# PA_CTRL_TOP.net
KiCad netlist of a schematic drawn in Altium Designer
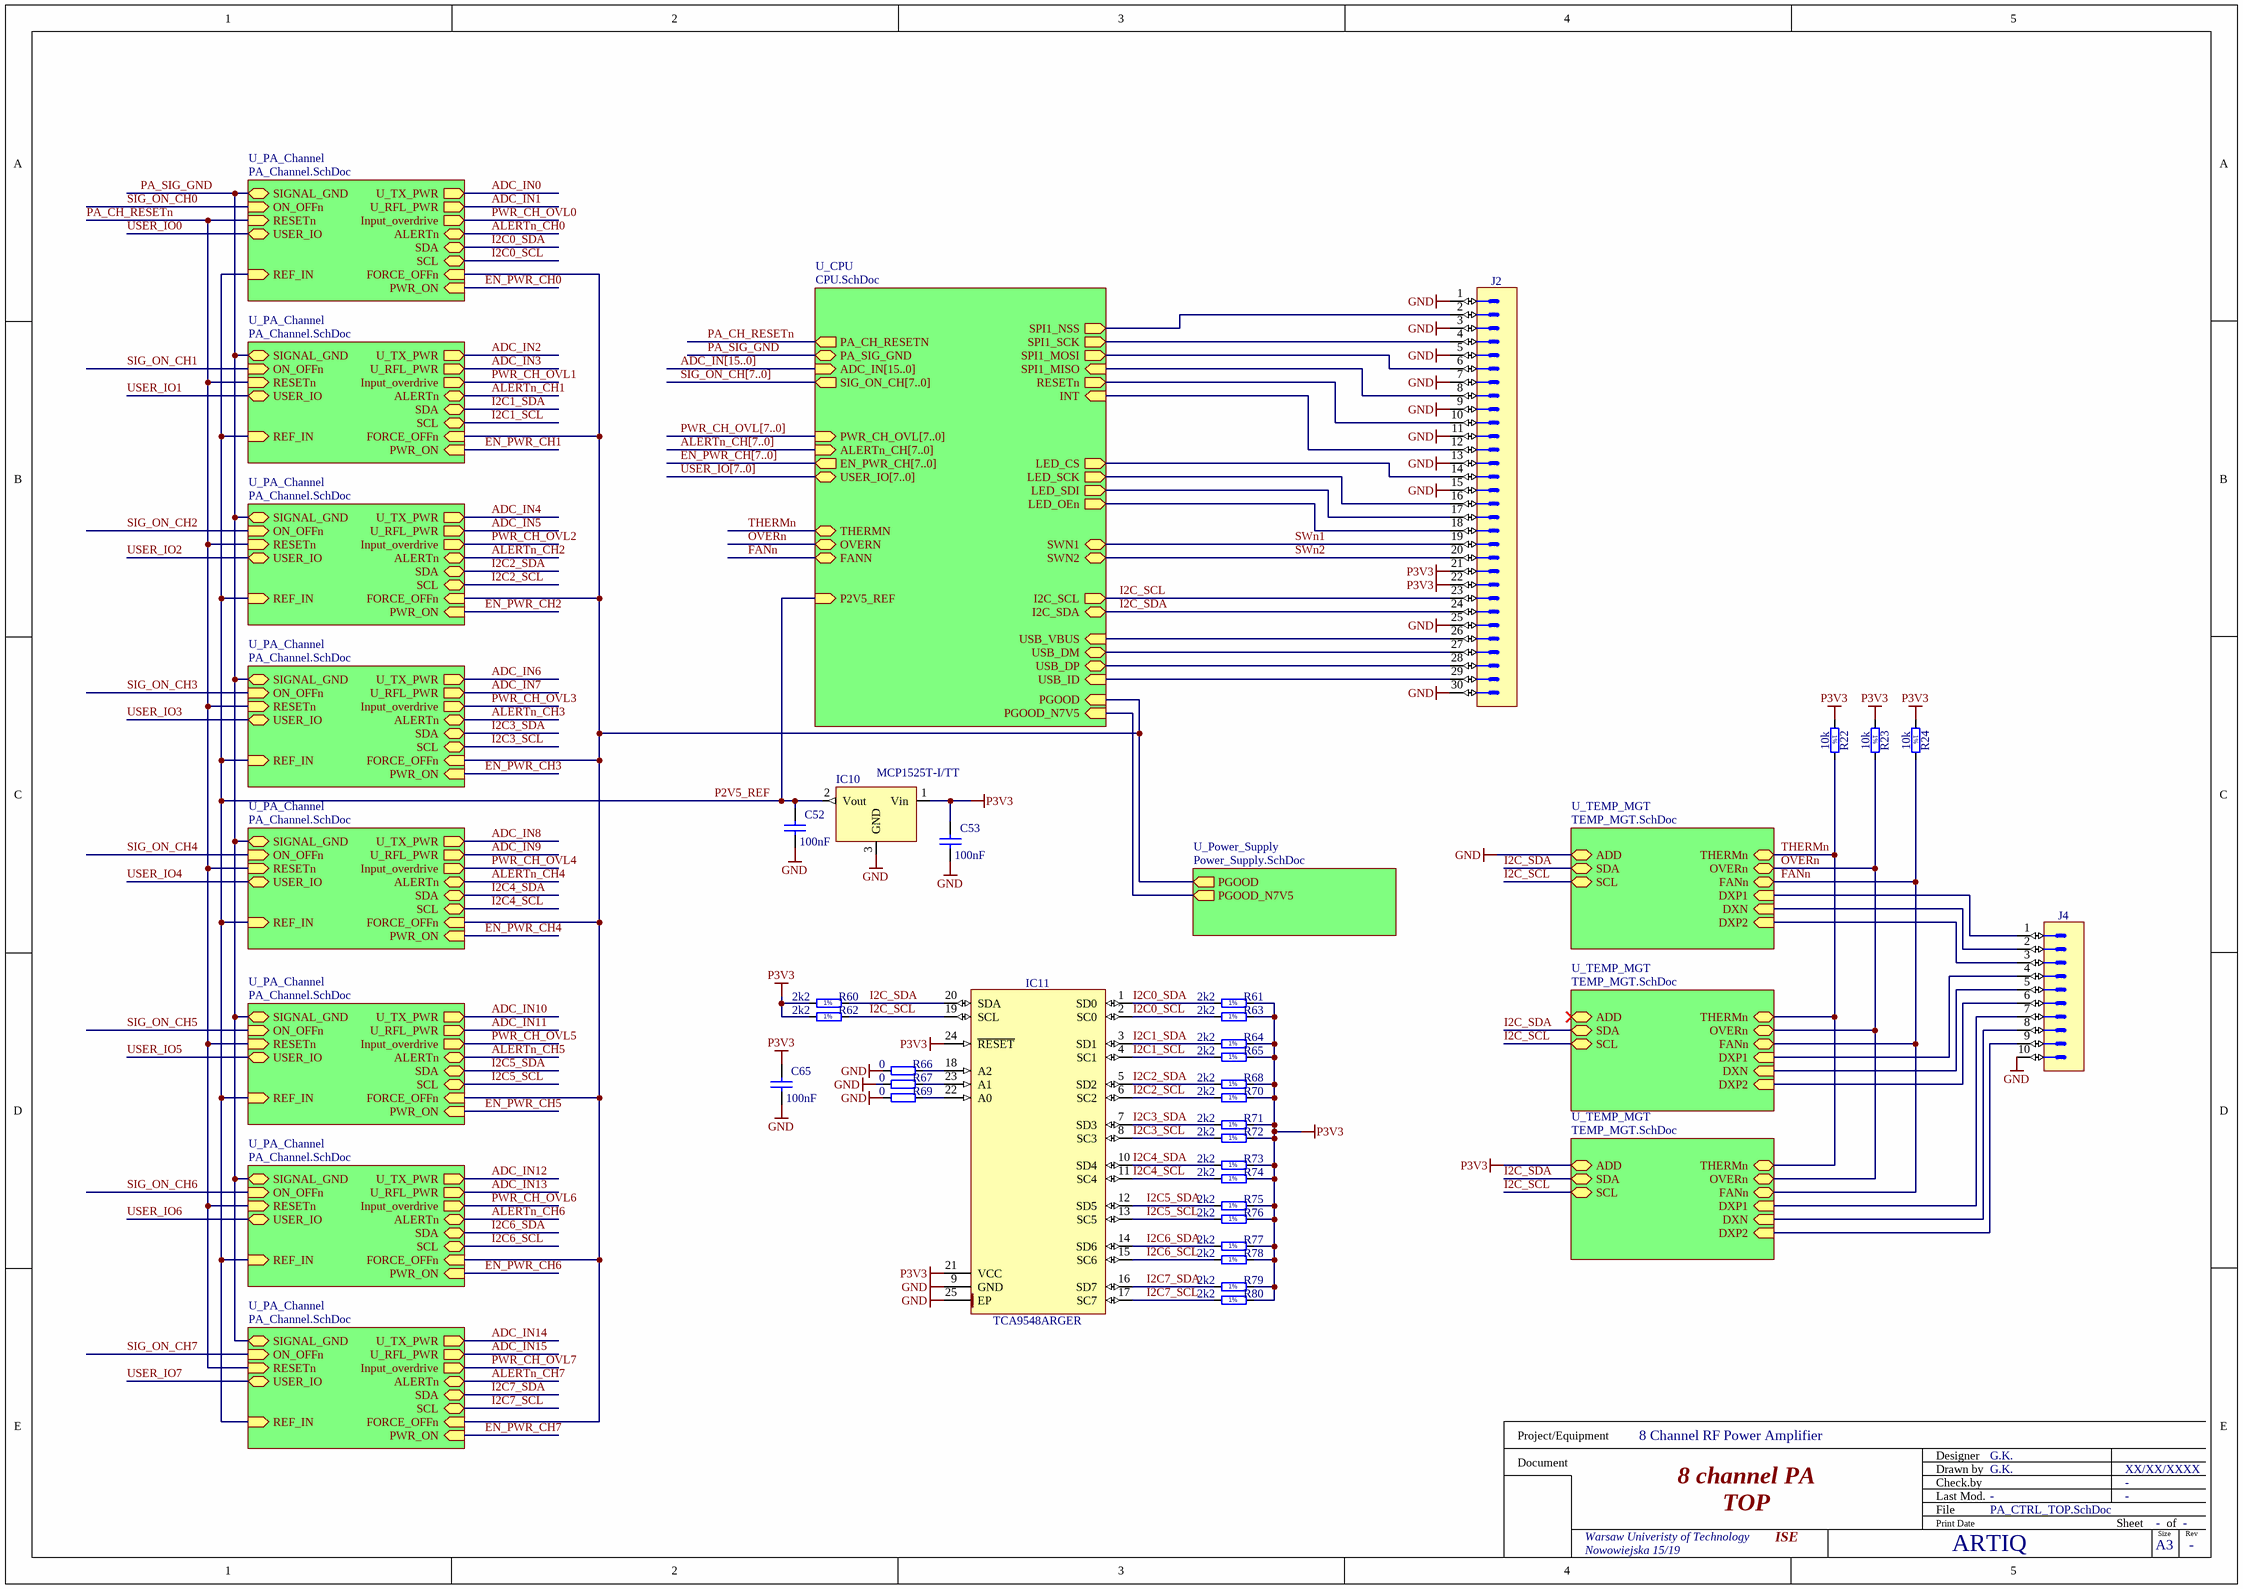
[diagram p0: PA_CTRL_TOP.SchDoc]

(export (version "E")
  (design (tool "Eeschema 10.0.6"))
  (components
    (comp (ref "C52")
      (value "100nF")
      (footprint "CAPC1005X55N")
      (description "Non-polarised capacitor")
      (fields
        (field (name "PART NUMBER") "CC0402_100NF_16V_10%_X7R")
        (field (name "VOLTAGE") "16V")
        (field (name "AUTHOR") "CERN DEM JLC")
      )
      (libsource (lib "Capacitors") (part "Capacitor - non polarized"))
    )
    (comp (ref "C53")
      (value "100nF")
      (footprint "CAPC1005X55N")
      (description "Non-polarised capacitor")
      (fields
        (field (name "PART NUMBER") "CC0402_100NF_16V_10%_X7R")
        (field (name "VOLTAGE") "16V")
        (field (name "AUTHOR") "CERN DEM JLC")
      )
      (libsource (lib "Capacitors") (part "Capacitor - non polarized"))
    )
    (comp (ref "C65")
      (value "100nF")
      (footprint "CAPC1005X55N")
      (description "Non-polarised capacitor")
      (fields
        (field (name "PART NUMBER") "CC0402_100NF_16V_10%_X7R")
        (field (name "VOLTAGE") "16V")
        (field (name "AUTHOR") "CERN DEM JLC")
      )
      (libsource (lib "Capacitors") (part "Capacitor - non polarized"))
    )
    (comp (ref "IC10")
      (value "MCP1525T-I/TT")
      (footprint "SOT95P251X112-3N")
      (description "2.5 voltage reference")
      (libsource (lib "LIBRARY_SCH") (part "REF_MCP1525"))
    )
    (comp (ref "IC11")
      (value "TCA9548ARGER")
      (footprint "QFN50P400X400X100-25N-S220")
      (description "Low Voltage 8-Channel I2C Switch With Reset")
      (fields (field (name "MANUFACTURER") "TEXAS INSTRUMENTS") (field (name "AUTHOR") "CERN DEM JLC"))
      (libsource (lib "ICs And Semiconductors") (part "TCA9548ARGER"))
    )
    (comp (ref "J2")
      (value "~")
      (footprint "3M_N2530-6002RB")
      (description "Connector 30 Male")
      (fields
        (field (name "PART NUMBER") "3M_N2530-6002RB")
        (field (name "MANUFACTURER") "3M")
        (field (name "AUTHOR") "CERN DEM JLC")
      )
      (libsource (lib "Connectors") (part "Connector 30 Male"))
    )
    (comp (ref "J4")
      (value "Header 10")
      (footprint "3M_N2510-6003RB")
      (description "Connector 10 Male")
      (fields
        (field (name "PART NUMBER") "3M_N2510-6003RB")
        (field (name "MANUFACTURER") "3M")
        (field (name "AUTHOR") "CERN DEM JLC")
      )
      (libsource (lib "Connectors") (part "Connector 10 Male"))
    )
    (comp (ref "R22")
      (value "10k")
      (footprint "RESC1005X40N")
      (description "Resistor - 1%")
      (fields
        (field (name "PART NUMBER") "R0402_10K_1%_0.0625W_100PPM")
        (field (name "POWER") "0.0625W")
        (field (name "AUTHOR") "CERN DEM JLC")
      )
      (libsource (lib "Resistors") (part "Resistor - 1%"))
    )
    (comp (ref "R23")
      (value "10k")
      (footprint "RESC1005X40N")
      (description "Resistor - 1%")
      (fields
        (field (name "PART NUMBER") "R0402_10K_1%_0.0625W_100PPM")
        (field (name "POWER") "0.0625W")
        (field (name "AUTHOR") "CERN DEM JLC")
      )
      (libsource (lib "Resistors") (part "Resistor - 1%"))
    )
    (comp (ref "R24")
      (value "10k")
      (footprint "RESC1005X40N")
      (description "Resistor - 1%")
      (fields
        (field (name "PART NUMBER") "R0402_10K_1%_0.0625W_100PPM")
        (field (name "POWER") "0.0625W")
        (field (name "AUTHOR") "CERN DEM JLC")
      )
      (libsource (lib "Resistors") (part "Resistor - 1%"))
    )
    (comp (ref "R60")
      (value "2k2")
      (footprint "RESC1005X40N")
      (description "Resistor - 1%")
      (fields
        (field (name "PART NUMBER") "R0402_2K2_1%_0.0625W_100PPM")
        (field (name "POWER") "0.0625W")
        (field (name "AUTHOR") "CERN DEM JLC")
      )
      (libsource (lib "Resistors") (part "Resistor - 1%"))
    )
    (comp (ref "R61")
      (value "2k2")
      (footprint "RESC1005X40N")
      (description "Resistor - 1%")
      (fields
        (field (name "PART NUMBER") "R0402_2K2_1%_0.0625W_100PPM")
        (field (name "POWER") "0.0625W")
        (field (name "AUTHOR") "CERN DEM JLC")
      )
      (libsource (lib "Resistors") (part "Resistor - 1%"))
    )
    (comp (ref "R62")
      (value "2k2")
      (footprint "RESC1005X40N")
      (description "Resistor - 1%")
      (fields
        (field (name "PART NUMBER") "R0402_2K2_1%_0.0625W_100PPM")
        (field (name "POWER") "0.0625W")
        (field (name "AUTHOR") "CERN DEM JLC")
      )
      (libsource (lib "Resistors") (part "Resistor - 1%"))
    )
    (comp (ref "R63")
      (value "2k2")
      (footprint "RESC1005X40N")
      (description "Resistor - 1%")
      (fields
        (field (name "PART NUMBER") "R0402_2K2_1%_0.0625W_100PPM")
        (field (name "POWER") "0.0625W")
        (field (name "AUTHOR") "CERN DEM JLC")
      )
      (libsource (lib "Resistors") (part "Resistor - 1%"))
    )
    (comp (ref "R64")
      (value "2k2")
      (footprint "RESC1005X40N")
      (description "Resistor - 1%")
      (fields
        (field (name "PART NUMBER") "R0402_2K2_1%_0.0625W_100PPM")
        (field (name "POWER") "0.0625W")
        (field (name "AUTHOR") "CERN DEM JLC")
      )
      (libsource (lib "Resistors") (part "Resistor - 1%"))
    )
    (comp (ref "R65")
      (value "2k2")
      (footprint "RESC1005X40N")
      (description "Resistor - 1%")
      (fields
        (field (name "PART NUMBER") "R0402_2K2_1%_0.0625W_100PPM")
        (field (name "POWER") "0.0625W")
        (field (name "AUTHOR") "CERN DEM JLC")
      )
      (libsource (lib "Resistors") (part "Resistor - 1%"))
    )
    (comp (ref "R66")
      (value "0")
      (footprint "RESC1005X40N")
      (description "Resistor")
      (fields
        (field (name "PART NUMBER") "R0402_0R_JUMPER")
        (field (name "MANUFACTURER") "GENERIC")
        (field (name "AUTHOR") "CERN DEM JLC")
      )
      (libsource (lib "Resistors") (part "Resistor"))
    )
    (comp (ref "R67")
      (value "0")
      (footprint "RESC1005X40N")
      (description "Resistor")
      (fields
        (field (name "PART NUMBER") "R0402_0R_JUMPER")
        (field (name "MANUFACTURER") "GENERIC")
        (field (name "AUTHOR") "CERN DEM JLC")
      )
      (libsource (lib "Resistors") (part "Resistor"))
    )
    (comp (ref "R68")
      (value "2k2")
      (footprint "RESC1005X40N")
      (description "Resistor - 1%")
      (fields
        (field (name "PART NUMBER") "R0402_2K2_1%_0.0625W_100PPM")
        (field (name "POWER") "0.0625W")
        (field (name "AUTHOR") "CERN DEM JLC")
      )
      (libsource (lib "Resistors") (part "Resistor - 1%"))
    )
    (comp (ref "R69")
      (value "0")
      (footprint "RESC1005X40N")
      (description "Resistor")
      (fields
        (field (name "PART NUMBER") "R0402_0R_JUMPER")
        (field (name "MANUFACTURER") "GENERIC")
        (field (name "AUTHOR") "CERN DEM JLC")
      )
      (libsource (lib "Resistors") (part "Resistor"))
    )
    (comp (ref "R70")
      (value "2k2")
      (footprint "RESC1005X40N")
      (description "Resistor - 1%")
      (fields
        (field (name "PART NUMBER") "R0402_2K2_1%_0.0625W_100PPM")
        (field (name "POWER") "0.0625W")
        (field (name "AUTHOR") "CERN DEM JLC")
      )
      (libsource (lib "Resistors") (part "Resistor - 1%"))
    )
    (comp (ref "R71")
      (value "2k2")
      (footprint "RESC1005X40N")
      (description "Resistor - 1%")
      (fields
        (field (name "PART NUMBER") "R0402_2K2_1%_0.0625W_100PPM")
        (field (name "POWER") "0.0625W")
        (field (name "AUTHOR") "CERN DEM JLC")
      )
      (libsource (lib "Resistors") (part "Resistor - 1%"))
    )
    (comp (ref "R72")
      (value "2k2")
      (footprint "RESC1005X40N")
      (description "Resistor - 1%")
      (fields
        (field (name "PART NUMBER") "R0402_2K2_1%_0.0625W_100PPM")
        (field (name "POWER") "0.0625W")
        (field (name "AUTHOR") "CERN DEM JLC")
      )
      (libsource (lib "Resistors") (part "Resistor - 1%"))
    )
    (comp (ref "R73")
      (value "2k2")
      (footprint "RESC1005X40N")
      (description "Resistor - 1%")
      (fields
        (field (name "PART NUMBER") "R0402_2K2_1%_0.0625W_100PPM")
        (field (name "POWER") "0.0625W")
        (field (name "AUTHOR") "CERN DEM JLC")
      )
      (libsource (lib "Resistors") (part "Resistor - 1%"))
    )
    (comp (ref "R74")
      (value "2k2")
      (footprint "RESC1005X40N")
      (description "Resistor - 1%")
      (fields
        (field (name "PART NUMBER") "R0402_2K2_1%_0.0625W_100PPM")
        (field (name "POWER") "0.0625W")
        (field (name "AUTHOR") "CERN DEM JLC")
      )
      (libsource (lib "Resistors") (part "Resistor - 1%"))
    )
    (comp (ref "R75")
      (value "2k2")
      (footprint "RESC1005X40N")
      (description "Resistor - 1%")
      (fields
        (field (name "PART NUMBER") "R0402_2K2_1%_0.0625W_100PPM")
        (field (name "POWER") "0.0625W")
        (field (name "AUTHOR") "CERN DEM JLC")
      )
      (libsource (lib "Resistors") (part "Resistor - 1%"))
    )
    (comp (ref "R76")
      (value "2k2")
      (footprint "RESC1005X40N")
      (description "Resistor - 1%")
      (fields
        (field (name "PART NUMBER") "R0402_2K2_1%_0.0625W_100PPM")
        (field (name "POWER") "0.0625W")
        (field (name "AUTHOR") "CERN DEM JLC")
      )
      (libsource (lib "Resistors") (part "Resistor - 1%"))
    )
    (comp (ref "R77")
      (value "2k2")
      (footprint "RESC1005X40N")
      (description "Resistor - 1%")
      (fields
        (field (name "PART NUMBER") "R0402_2K2_1%_0.0625W_100PPM")
        (field (name "POWER") "0.0625W")
        (field (name "AUTHOR") "CERN DEM JLC")
      )
      (libsource (lib "Resistors") (part "Resistor - 1%"))
    )
    (comp (ref "R78")
      (value "2k2")
      (footprint "RESC1005X40N")
      (description "Resistor - 1%")
      (fields
        (field (name "PART NUMBER") "R0402_2K2_1%_0.0625W_100PPM")
        (field (name "POWER") "0.0625W")
        (field (name "AUTHOR") "CERN DEM JLC")
      )
      (libsource (lib "Resistors") (part "Resistor - 1%"))
    )
    (comp (ref "R79")
      (value "2k2")
      (footprint "RESC1005X40N")
      (description "Resistor - 1%")
      (fields
        (field (name "PART NUMBER") "R0402_2K2_1%_0.0625W_100PPM")
        (field (name "POWER") "0.0625W")
        (field (name "AUTHOR") "CERN DEM JLC")
      )
      (libsource (lib "Resistors") (part "Resistor - 1%"))
    )
    (comp (ref "R80")
      (value "2k2")
      (footprint "RESC1005X40N")
      (description "Resistor - 1%")
      (fields
        (field (name "PART NUMBER") "R0402_2K2_1%_0.0625W_100PPM")
        (field (name "POWER") "0.0625W")
        (field (name "AUTHOR") "CERN DEM JLC")
      )
      (libsource (lib "Resistors") (part "Resistor - 1%"))
    )
  )
  (nets
    (net (code "28") (name "/DXN") (class "Default")
      (node (ref "J4") (pin "5") (pinfunction "5_5") (pintype "bidirectional"))
    )
    (net (code "29") (name "/DXN_1") (class "Default")
      (node (ref "J4") (pin "8") (pinfunction "8_8") (pintype "bidirectional"))
    )
    (net (code "30") (name "/DXN_2") (class "Default")
      (node (ref "J4") (pin "2") (pinfunction "2_2") (pintype "bidirectional"))
    )
    (net (code "31") (name "/DXP1") (class "Default")
      (node (ref "J4") (pin "4") (pinfunction "4_4") (pintype "bidirectional"))
    )
    (net (code "32") (name "/DXP1_1") (class "Default")
      (node (ref "J4") (pin "7") (pinfunction "7_7") (pintype "bidirectional"))
    )
    (net (code "33") (name "/DXP1_2") (class "Default")
      (node (ref "J4") (pin "1") (pinfunction "1_1") (pintype "bidirectional"))
    )
    (net (code "34") (name "/DXP2") (class "Default")
      (node (ref "J4") (pin "6") (pinfunction "6_6") (pintype "bidirectional"))
    )
    (net (code "35") (name "/DXP2_1") (class "Default")
      (node (ref "J4") (pin "9") (pinfunction "9_9") (pintype "bidirectional"))
    )
    (net (code "36") (name "/DXP2_2") (class "Default")
      (node (ref "J4") (pin "3") (pinfunction "3_3") (pintype "bidirectional"))
    )
    (net (code "46") (name "/FANn") (class "Default")
      (node (ref "R24") (pin "2") (pinfunction "2_2") (pintype "passive"))
    )
    (net (code "47") (name "/I2C0_SCL") (class "Default")
      (node (ref "IC11") (pin "2") (pinfunction "SC0_2") (pintype "bidirectional"))
      (node (ref "R63") (pin "1") (pinfunction "1_1") (pintype "passive"))
    )
    (net (code "48") (name "/I2C0_SDA") (class "Default")
      (node (ref "IC11") (pin "1") (pinfunction "SD0_1") (pintype "bidirectional"))
      (node (ref "R61") (pin "1") (pinfunction "1_1") (pintype "passive"))
    )
    (net (code "49") (name "/I2C1_SCL") (class "Default")
      (node (ref "IC11") (pin "4") (pinfunction "SC1_4") (pintype "bidirectional"))
      (node (ref "R65") (pin "1") (pinfunction "1_1") (pintype "passive"))
    )
    (net (code "50") (name "/I2C1_SDA") (class "Default")
      (node (ref "IC11") (pin "3") (pinfunction "SD1_3") (pintype "bidirectional"))
      (node (ref "R64") (pin "1") (pinfunction "1_1") (pintype "passive"))
    )
    (net (code "51") (name "/I2C2_SCL") (class "Default")
      (node (ref "IC11") (pin "6") (pinfunction "SC2_6") (pintype "bidirectional"))
      (node (ref "R70") (pin "1") (pinfunction "1_1") (pintype "passive"))
    )
    (net (code "52") (name "/I2C2_SDA") (class "Default")
      (node (ref "IC11") (pin "5") (pinfunction "SD2_5") (pintype "bidirectional"))
      (node (ref "R68") (pin "1") (pinfunction "1_1") (pintype "passive"))
    )
    (net (code "53") (name "/I2C3_SCL") (class "Default")
      (node (ref "IC11") (pin "8") (pinfunction "SC3_8") (pintype "bidirectional"))
      (node (ref "R72") (pin "1") (pinfunction "1_1") (pintype "passive"))
    )
    (net (code "54") (name "/I2C3_SDA") (class "Default")
      (node (ref "IC11") (pin "7") (pinfunction "SD3_7") (pintype "bidirectional"))
      (node (ref "R71") (pin "1") (pinfunction "1_1") (pintype "passive"))
    )
    (net (code "55") (name "/I2C4_SCL") (class "Default")
      (node (ref "IC11") (pin "11") (pinfunction "SC4_11") (pintype "bidirectional"))
      (node (ref "R74") (pin "1") (pinfunction "1_1") (pintype "passive"))
    )
    (net (code "56") (name "/I2C4_SDA") (class "Default")
      (node (ref "IC11") (pin "10") (pinfunction "SD4_10") (pintype "bidirectional"))
      (node (ref "R73") (pin "1") (pinfunction "1_1") (pintype "passive"))
    )
    (net (code "57") (name "/I2C5_SCL") (class "Default")
      (node (ref "IC11") (pin "13") (pinfunction "SC5_13") (pintype "bidirectional"))
      (node (ref "R76") (pin "1") (pinfunction "1_1") (pintype "passive"))
    )
    (net (code "58") (name "/I2C5_SDA") (class "Default")
      (node (ref "IC11") (pin "12") (pinfunction "SD5_12") (pintype "bidirectional"))
      (node (ref "R75") (pin "1") (pinfunction "1_1") (pintype "passive"))
    )
    (net (code "59") (name "/I2C6_SCL") (class "Default")
      (node (ref "IC11") (pin "15") (pinfunction "SC6_15") (pintype "bidirectional"))
      (node (ref "R78") (pin "1") (pinfunction "1_1") (pintype "passive"))
    )
    (net (code "60") (name "/I2C6_SDA") (class "Default")
      (node (ref "IC11") (pin "14") (pinfunction "SD6_14") (pintype "bidirectional"))
      (node (ref "R77") (pin "1") (pinfunction "1_1") (pintype "passive"))
    )
    (net (code "61") (name "/I2C7_SCL") (class "Default")
      (node (ref "IC11") (pin "17") (pinfunction "SC7_17") (pintype "bidirectional"))
      (node (ref "R80") (pin "1") (pinfunction "1_1") (pintype "passive"))
    )
    (net (code "62") (name "/I2C7_SDA") (class "Default")
      (node (ref "IC11") (pin "16") (pinfunction "SD7_16") (pintype "bidirectional"))
      (node (ref "R79") (pin "1") (pinfunction "1_1") (pintype "passive"))
    )
    (net (code "63") (name "/I2C_SCL") (class "Default")
      (node (ref "IC11") (pin "19") (pinfunction "SCL_19") (pintype "bidirectional"))
      (node (ref "J2") (pin "23") (pinfunction "23_23") (pintype "bidirectional"))
      (node (ref "R62") (pin "2") (pinfunction "2_2") (pintype "passive"))
    )
    (net (code "64") (name "/I2C_SDA") (class "Default")
      (node (ref "IC11") (pin "20") (pinfunction "SDA_20") (pintype "bidirectional"))
      (node (ref "J2") (pin "24") (pinfunction "24_24") (pintype "bidirectional"))
      (node (ref "R60") (pin "2") (pinfunction "2_2") (pintype "passive"))
    )
    (net (code "65") (name "/INT") (class "Default")
      (node (ref "J2") (pin "12") (pinfunction "12_12") (pintype "bidirectional"))
    )
    (net (code "66") (name "/LED_CS") (class "Default")
      (node (ref "J2") (pin "14") (pinfunction "14_14") (pintype "bidirectional"))
    )
    (net (code "67") (name "/LED_OEn") (class "Default")
      (node (ref "J2") (pin "18") (pinfunction "18_18") (pintype "bidirectional"))
    )
    (net (code "68") (name "/LED_SCK") (class "Default")
      (node (ref "J2") (pin "16") (pinfunction "16_16") (pintype "bidirectional"))
    )
    (net (code "69") (name "/LED_SDI") (class "Default")
      (node (ref "J2") (pin "17") (pinfunction "17_17") (pintype "bidirectional"))
    )
    (net (code "70") (name "/OVERn") (class "Default")
      (node (ref "R23") (pin "2") (pinfunction "2_2") (pintype "passive"))
    )
    (net (code "71") (name "/P2V5_REF") (class "Default")
      (node (ref "C52") (pin "1") (pinfunction "1_1") (pintype "passive"))
      (node (ref "IC10") (pin "2") (pinfunction "Vout_2") (pintype "output"))
    )
    (net (code "85") (name "/RESETn") (class "Default")
      (node (ref "J2") (pin "10") (pinfunction "10_10") (pintype "bidirectional"))
    )
    (net (code "95") (name "/SPI1_MISO") (class "Default")
      (node (ref "J2") (pin "8") (pinfunction "8_8") (pintype "bidirectional"))
    )
    (net (code "96") (name "/SPI1_MOSI") (class "Default")
      (node (ref "J2") (pin "6") (pinfunction "6_6") (pintype "bidirectional"))
    )
    (net (code "97") (name "/SPI1_NSS") (class "Default")
      (node (ref "J2") (pin "2") (pinfunction "2_2") (pintype "bidirectional"))
    )
    (net (code "98") (name "/SPI1_SCK") (class "Default")
      (node (ref "J2") (pin "4") (pinfunction "4_4") (pintype "bidirectional"))
    )
    (net (code "99") (name "/SWn1") (class "Default")
      (node (ref "J2") (pin "19") (pinfunction "19_19") (pintype "bidirectional"))
    )
    (net (code "100") (name "/SWn2") (class "Default")
      (node (ref "J2") (pin "20") (pinfunction "20_20") (pintype "bidirectional"))
    )
    (net (code "101") (name "/THERMn") (class "Default")
      (node (ref "R22") (pin "2") (pinfunction "2_2") (pintype "passive"))
    )
    (net (code "102") (name "/USB_DM") (class "Default")
      (node (ref "J2") (pin "27") (pinfunction "27_27") (pintype "bidirectional"))
    )
    (net (code "103") (name "/USB_DP") (class "Default")
      (node (ref "J2") (pin "28") (pinfunction "28_28") (pintype "bidirectional"))
    )
    (net (code "104") (name "/USB_ID") (class "Default")
      (node (ref "J2") (pin "29") (pinfunction "29_29") (pintype "bidirectional"))
    )
    (net (code "105") (name "/USB_VBUS") (class "Default")
      (node (ref "J2") (pin "26") (pinfunction "26_26") (pintype "bidirectional"))
    )
    (net (code "115") (name "GND") (class "Default")
      (node (ref "C52") (pin "2") (pinfunction "2_2") (pintype "passive"))
      (node (ref "C53") (pin "2") (pinfunction "2_2") (pintype "passive"))
      (node (ref "C65") (pin "2") (pinfunction "2_2") (pintype "passive"))
      (node (ref "IC10") (pin "3") (pinfunction "GND_3") (pintype "power_in"))
      (node (ref "IC11") (pin "25") (pinfunction "EP_25") (pintype "power_in"))
      (node (ref "IC11") (pin "9") (pinfunction "GND_9") (pintype "power_in"))
      (node (ref "J2") (pin "1") (pinfunction "1_1") (pintype "bidirectional"))
      (node (ref "J2") (pin "11") (pinfunction "11_11") (pintype "bidirectional"))
      (node (ref "J2") (pin "13") (pinfunction "13_13") (pintype "bidirectional"))
      (node (ref "J2") (pin "15") (pinfunction "15_15") (pintype "bidirectional"))
      (node (ref "J2") (pin "25") (pinfunction "25_25") (pintype "bidirectional"))
      (node (ref "J2") (pin "3") (pinfunction "3_3") (pintype "bidirectional"))
      (node (ref "J2") (pin "30") (pinfunction "30_30") (pintype "bidirectional"))
      (node (ref "J2") (pin "5") (pinfunction "5_5") (pintype "bidirectional"))
      (node (ref "J2") (pin "7") (pinfunction "7_7") (pintype "bidirectional"))
      (node (ref "J2") (pin "9") (pinfunction "9_9") (pintype "bidirectional"))
      (node (ref "J4") (pin "10") (pinfunction "10_10") (pintype "bidirectional"))
      (node (ref "R66") (pin "1") (pinfunction "1_1") (pintype "passive"))
      (node (ref "R67") (pin "1") (pinfunction "1_1") (pintype "passive"))
      (node (ref "R69") (pin "1") (pinfunction "1_1") (pintype "passive"))
    )
    (net (code "116") (name "Net-(IC11-A0)") (class "Default")
      (node (ref "IC11") (pin "22") (pinfunction "A0_22") (pintype "input"))
      (node (ref "R69") (pin "2") (pinfunction "2_2") (pintype "passive"))
    )
    (net (code "117") (name "Net-(IC11-A1)") (class "Default")
      (node (ref "IC11") (pin "23") (pinfunction "A1_23") (pintype "input"))
      (node (ref "R67") (pin "2") (pinfunction "2_2") (pintype "passive"))
    )
    (net (code "118") (name "Net-(IC11-A2)") (class "Default")
      (node (ref "IC11") (pin "18") (pinfunction "A2_18") (pintype "input"))
      (node (ref "R66") (pin "2") (pinfunction "2_2") (pintype "passive"))
    )
    (net (code "119") (name "P3V3") (class "Default")
      (node (ref "C53") (pin "1") (pinfunction "1_1") (pintype "passive"))
      (node (ref "C65") (pin "1") (pinfunction "1_1") (pintype "passive"))
      (node (ref "IC10") (pin "1") (pinfunction "Vin_1") (pintype "power_in"))
      (node (ref "IC11") (pin "21") (pinfunction "VCC_21") (pintype "power_in"))
      (node (ref "IC11") (pin "24") (pinfunction "~{RESET}_24") (pintype "input"))
      (node (ref "J2") (pin "21") (pinfunction "21_21") (pintype "bidirectional"))
      (node (ref "J2") (pin "22") (pinfunction "22_22") (pintype "bidirectional"))
      (node (ref "R22") (pin "1") (pinfunction "1_1") (pintype "passive"))
      (node (ref "R23") (pin "1") (pinfunction "1_1") (pintype "passive"))
      (node (ref "R24") (pin "1") (pinfunction "1_1") (pintype "passive"))
      (node (ref "R60") (pin "1") (pinfunction "1_1") (pintype "passive"))
      (node (ref "R61") (pin "2") (pinfunction "2_2") (pintype "passive"))
      (node (ref "R62") (pin "1") (pinfunction "1_1") (pintype "passive"))
      (node (ref "R63") (pin "2") (pinfunction "2_2") (pintype "passive"))
      (node (ref "R64") (pin "2") (pinfunction "2_2") (pintype "passive"))
      (node (ref "R65") (pin "2") (pinfunction "2_2") (pintype "passive"))
      (node (ref "R68") (pin "2") (pinfunction "2_2") (pintype "passive"))
      (node (ref "R70") (pin "2") (pinfunction "2_2") (pintype "passive"))
      (node (ref "R71") (pin "2") (pinfunction "2_2") (pintype "passive"))
      (node (ref "R72") (pin "2") (pinfunction "2_2") (pintype "passive"))
      (node (ref "R73") (pin "2") (pinfunction "2_2") (pintype "passive"))
      (node (ref "R74") (pin "2") (pinfunction "2_2") (pintype "passive"))
      (node (ref "R75") (pin "2") (pinfunction "2_2") (pintype "passive"))
      (node (ref "R76") (pin "2") (pinfunction "2_2") (pintype "passive"))
      (node (ref "R77") (pin "2") (pinfunction "2_2") (pintype "passive"))
      (node (ref "R78") (pin "2") (pinfunction "2_2") (pintype "passive"))
      (node (ref "R79") (pin "2") (pinfunction "2_2") (pintype "passive"))
      (node (ref "R80") (pin "2") (pinfunction "2_2") (pintype "passive"))
    )
  )
)
